# Adafruit_Latching_Relay_FeatherWing.net
KiCad netlist of a schematic drawn in EAGLE
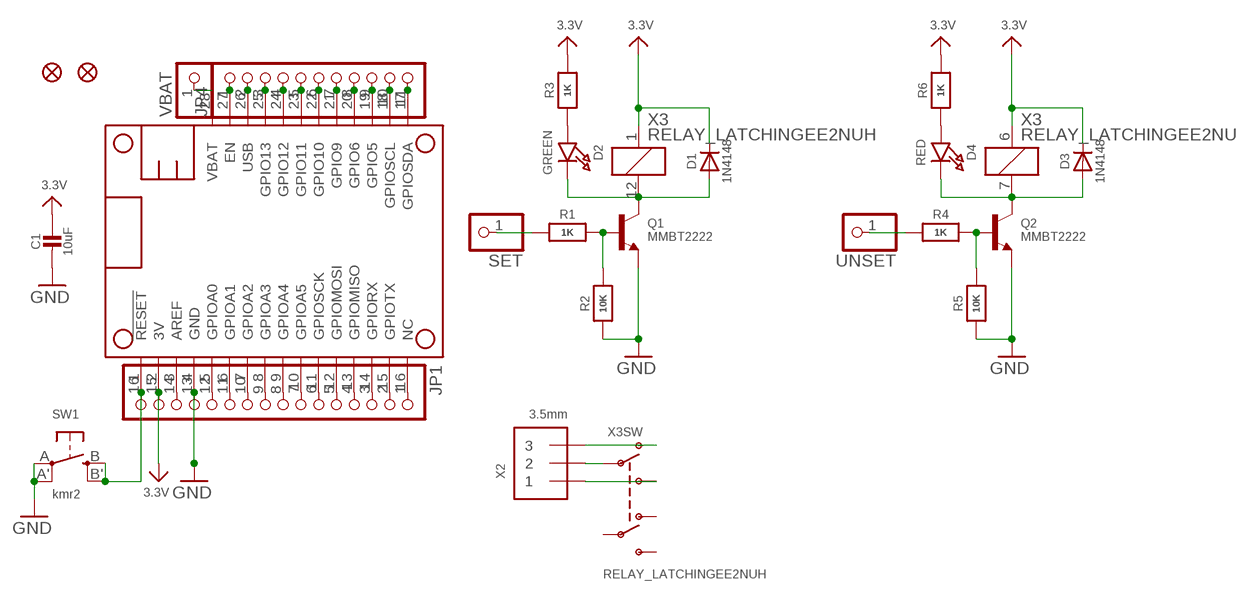
[diagram p0: schematic, sheet 1]

(export (version "E")
  (design (tool "Eeschema 10.0.6"))
  (components
    (comp (ref "C1")
      (value "10uF")
      (footprint "eagle-import:0805-NO")
      (libsource (lib "eagle-import") (part "CAP_CERAMIC0805-NOOUTLINE"))
    )
    (comp (ref "D1")
      (value "1N4148")
      (footprint "eagle-import:SOD-323")
      (libsource (lib "eagle-import") (part "DIODESOD-323"))
    )
    (comp (ref "D2")
      (value "GREEN")
      (footprint "eagle-import:CHIPLED_0805_NOOUTLINE")
      (libsource (lib "eagle-import") (part "LED0805_NOOUTLINE"))
    )
    (comp (ref "D3")
      (value "1N4148")
      (footprint "eagle-import:SOD-323")
      (libsource (lib "eagle-import") (part "DIODESOD-323"))
    )
    (comp (ref "D4")
      (value "RED")
      (footprint "eagle-import:CHIPLED_0805_NOOUTLINE")
      (libsource (lib "eagle-import") (part "LED0805_NOOUTLINE"))
    )
    (comp (ref "FID2")
      (value "FIDUCIAL\"\"")
      (footprint "eagle-import:FIDUCIAL_1MM")
      (libsource (lib "eagle-import") (part "FIDUCIAL{dblquote}{dblquote}"))
    )
    (comp (ref "FID3")
      (value "FIDUCIAL\"\"")
      (footprint "eagle-import:FIDUCIAL_1MM")
      (libsource (lib "eagle-import") (part "FIDUCIAL{dblquote}{dblquote}"))
    )
    (comp (ref "JP1")
      (value "HEADER-1X16ROUND")
      (footprint "eagle-import:1X16_ROUND")
      (libsource (lib "eagle-import") (part "HEADER-1X16ROUND"))
    )
    (comp (ref "JP4")
      (value "HEADER-1X11")
      (footprint "eagle-import:1X11_ROUND")
      (libsource (lib "eagle-import") (part "HEADER-1X11"))
    )
    (comp (ref "MS1")
      (value "MICROSHIELD")
      (footprint "eagle-import:MICROSHIELD")
      (libsource (lib "eagle-import") (part "MICROSHIELD"))
    )
    (comp (ref "Q1")
      (value "MMBT2222")
      (footprint "eagle-import:SOT23-R")
      (libsource (lib "eagle-import") (part "TRANSISTOR_NPN"))
    )
    (comp (ref "Q2")
      (value "MMBT2222")
      (footprint "eagle-import:SOT23-R")
      (libsource (lib "eagle-import") (part "TRANSISTOR_NPN"))
    )
    (comp (ref "R1")
      (value "1K")
      (footprint "eagle-import:0805-NO")
      (libsource (lib "eagle-import") (part "RESISTOR0805_NOOUTLINE"))
    )
    (comp (ref "R2")
      (value "10K")
      (footprint "eagle-import:0805-NO")
      (libsource (lib "eagle-import") (part "RESISTOR0805_NOOUTLINE"))
    )
    (comp (ref "R3")
      (value "1K")
      (footprint "eagle-import:0805-NO")
      (libsource (lib "eagle-import") (part "RESISTOR0805_NOOUTLINE"))
    )
    (comp (ref "R4")
      (value "1K")
      (footprint "eagle-import:0805-NO")
      (libsource (lib "eagle-import") (part "RESISTOR0805_NOOUTLINE"))
    )
    (comp (ref "R5")
      (value "10K")
      (footprint "eagle-import:0805-NO")
      (libsource (lib "eagle-import") (part "RESISTOR0805_NOOUTLINE"))
    )
    (comp (ref "R6")
      (value "1K")
      (footprint "eagle-import:0805-NO")
      (libsource (lib "eagle-import") (part "RESISTOR0805_NOOUTLINE"))
    )
    (comp (ref "SET")
      (value "HEADER-1X1ROUND")
      (footprint "eagle-import:1X01_ROUND")
      (libsource (lib "eagle-import") (part "HEADER-1X1ROUND"))
    )
    (comp (ref "SW1")
      (value "kmr2")
      (footprint "eagle-import:BTN_KMR2_4.6X2.8")
      (libsource (lib "eagle-import") (part "SWITCH_TACT_SMT4.6X2.8"))
    )
    (comp (ref "UNSET")
      (value "HEADER-1X1ROUND")
      (footprint "eagle-import:1X01_ROUND")
      (libsource (lib "eagle-import") (part "HEADER-1X1ROUND"))
    )
    (comp (ref "VBAT")
      (value "HEADER-1X1ROUND")
      (footprint "eagle-import:1X01_ROUND")
      (libsource (lib "eagle-import") (part "HEADER-1X1ROUND"))
    )
    (comp (ref "X2")
      (value "3.5mm")
      (footprint "eagle-import:TERMBLOCK_1X3-3.5MM")
      (libsource (lib "eagle-import") (part "TERMBLOCK_1X3"))
    )
    (comp (ref "X3")
      (value "RELAY_LATCHINGEE2NUH")
      (footprint "eagle-import:RELAY_EE2_LATCH")
      (libsource (lib "eagle-import") (part "RELAY_LATCHINGEE2NUH"))
    )
  )
  (nets
    (net (code "1") (name "3.3V") (class "Default")
      (node (ref "C1") (pin "1") (pinfunction "1_1") (pintype "passive"))
      (node (ref "D1") (pin "C") (pinfunction "C_C") (pintype "passive"))
      (node (ref "D3") (pin "C") (pinfunction "C_C") (pintype "passive"))
      (node (ref "JP1") (pin "15") (pinfunction "15_15") (pintype "passive"))
      (node (ref "MS1") (pin "2") (pinfunction "3V_2") (pintype "power_in"))
      (node (ref "R3") (pin "2") (pinfunction "2_2") (pintype "passive"))
      (node (ref "R6") (pin "2") (pinfunction "2_2") (pintype "passive"))
      (node (ref "X3") (pin "1") (pinfunction "1_1") (pintype "passive"))
      (node (ref "X3") (pin "6") (pinfunction "1_6") (pintype "passive"))
    )
    (net (code "2") (name "GND") (class "Default")
      (node (ref "C1") (pin "2") (pinfunction "2_2") (pintype "passive"))
      (node (ref "JP1") (pin "13") (pinfunction "13_13") (pintype "passive"))
      (node (ref "MS1") (pin "4") (pinfunction "GND_4") (pintype "power_in"))
      (node (ref "Q1") (pin "2") (pinfunction "E_2") (pintype "passive"))
      (node (ref "Q2") (pin "2") (pinfunction "E_2") (pintype "passive"))
      (node (ref "R2") (pin "1") (pinfunction "1_1") (pintype "passive"))
      (node (ref "R5") (pin "1") (pinfunction "1_1") (pintype "passive"))
      (node (ref "SW1") (pin "A") (pinfunction "P_A") (pintype "passive"))
      (node (ref "SW1") (pin "A'") (pinfunction "P1_A'") (pintype "passive"))
    )
    (net (code "3") (name "Net-(D2-PadA)") (class "Default")
      (node (ref "D2") (pin "A") (pinfunction "A_A") (pintype "passive"))
      (node (ref "R3") (pin "1") (pinfunction "1_1") (pintype "passive"))
    )
    (net (code "4") (name "Net-(D4-PadA)") (class "Default")
      (node (ref "D4") (pin "A") (pinfunction "A_A") (pintype "passive"))
      (node (ref "R6") (pin "1") (pinfunction "1_1") (pintype "passive"))
    )
    (net (code "5") (name "Net-(MS1-AREF)") (class "Default")
      (node (ref "JP1") (pin "14") (pinfunction "14_14") (pintype "passive"))
      (node (ref "MS1") (pin "3") (pinfunction "AREF_3") (pintype "passive"))
    )
    (net (code "6") (name "Net-(MS1-EN)") (class "Default")
      (node (ref "JP4") (pin "1") (pinfunction "1_1") (pintype "passive"))
      (node (ref "MS1") (pin "27") (pinfunction "EN_27") (pintype "passive"))
    )
    (net (code "7") (name "Net-(MS1-GPIO5)") (class "Default")
      (node (ref "JP4") (pin "9") (pinfunction "9_9") (pintype "passive"))
      (node (ref "MS1") (pin "19") (pinfunction "GPIO5_19") (pintype "bidirectional"))
    )
    (net (code "8") (name "Net-(MS1-GPIO6)") (class "Default")
      (node (ref "JP4") (pin "8") (pinfunction "8_8") (pintype "passive"))
      (node (ref "MS1") (pin "20") (pinfunction "GPIO6_20") (pintype "bidirectional"))
    )
    (net (code "9") (name "Net-(MS1-GPIO9)") (class "Default")
      (node (ref "JP4") (pin "7") (pinfunction "7_7") (pintype "passive"))
      (node (ref "MS1") (pin "21") (pinfunction "GPIO9_21") (pintype "bidirectional"))
    )
    (net (code "10") (name "Net-(MS1-GPIO10)") (class "Default")
      (node (ref "JP4") (pin "6") (pinfunction "6_6") (pintype "passive"))
      (node (ref "MS1") (pin "22") (pinfunction "GPIO10_22") (pintype "bidirectional"))
    )
    (net (code "11") (name "Net-(MS1-GPIO11)") (class "Default")
      (node (ref "JP4") (pin "5") (pinfunction "5_5") (pintype "passive"))
      (node (ref "MS1") (pin "23") (pinfunction "GPIO11_23") (pintype "bidirectional"))
    )
    (net (code "12") (name "Net-(MS1-GPIO12)") (class "Default")
      (node (ref "JP4") (pin "4") (pinfunction "4_4") (pintype "passive"))
      (node (ref "MS1") (pin "24") (pinfunction "GPIO12_24") (pintype "bidirectional"))
    )
    (net (code "13") (name "Net-(MS1-GPIO13)") (class "Default")
      (node (ref "JP4") (pin "3") (pinfunction "3_3") (pintype "passive"))
      (node (ref "MS1") (pin "25") (pinfunction "GPIO13_25") (pintype "bidirectional"))
    )
    (net (code "14") (name "Net-(MS1-GPIOA0)") (class "Default")
      (node (ref "JP1") (pin "12") (pinfunction "12_12") (pintype "passive"))
      (node (ref "MS1") (pin "5") (pinfunction "GPIOA0_5") (pintype "bidirectional"))
    )
    (net (code "15") (name "Net-(MS1-GPIOA1)") (class "Default")
      (node (ref "JP1") (pin "11") (pinfunction "11_11") (pintype "passive"))
      (node (ref "MS1") (pin "6") (pinfunction "GPIOA1_6") (pintype "bidirectional"))
    )
    (net (code "16") (name "Net-(MS1-GPIOA2)") (class "Default")
      (node (ref "JP1") (pin "10") (pinfunction "10_10") (pintype "passive"))
      (node (ref "MS1") (pin "7") (pinfunction "GPIOA2_7") (pintype "bidirectional"))
    )
    (net (code "17") (name "Net-(MS1-GPIOA3)") (class "Default")
      (node (ref "JP1") (pin "9") (pinfunction "9_9") (pintype "passive"))
      (node (ref "MS1") (pin "8") (pinfunction "GPIOA3_8") (pintype "bidirectional"))
    )
    (net (code "18") (name "Net-(MS1-GPIOA4)") (class "Default")
      (node (ref "JP1") (pin "8") (pinfunction "8_8") (pintype "passive"))
      (node (ref "MS1") (pin "9") (pinfunction "GPIOA4_9") (pintype "bidirectional"))
    )
    (net (code "19") (name "Net-(MS1-GPIOA5)") (class "Default")
      (node (ref "JP1") (pin "7") (pinfunction "7_7") (pintype "passive"))
      (node (ref "MS1") (pin "10") (pinfunction "GPIOA5_10") (pintype "bidirectional"))
    )
    (net (code "20") (name "Net-(MS1-GPIOMISO)") (class "Default")
      (node (ref "JP1") (pin "4") (pinfunction "4_4") (pintype "passive"))
      (node (ref "MS1") (pin "13") (pinfunction "GPIOMISO_13") (pintype "bidirectional"))
    )
    (net (code "21") (name "Net-(MS1-GPIOMOSI)") (class "Default")
      (node (ref "JP1") (pin "5") (pinfunction "5_5") (pintype "passive"))
      (node (ref "MS1") (pin "12") (pinfunction "GPIOMOSI_12") (pintype "bidirectional"))
    )
    (net (code "22") (name "Net-(MS1-GPIORX)") (class "Default")
      (node (ref "JP1") (pin "3") (pinfunction "3_3") (pintype "passive"))
      (node (ref "MS1") (pin "14") (pinfunction "GPIORX_14") (pintype "bidirectional"))
    )
    (net (code "23") (name "Net-(MS1-GPIOSCK)") (class "Default")
      (node (ref "JP1") (pin "6") (pinfunction "6_6") (pintype "passive"))
      (node (ref "MS1") (pin "11") (pinfunction "GPIOSCK_11") (pintype "bidirectional"))
    )
    (net (code "24") (name "Net-(MS1-GPIOSCL)") (class "Default")
      (node (ref "JP4") (pin "10") (pinfunction "10_10") (pintype "passive"))
      (node (ref "MS1") (pin "18") (pinfunction "GPIOSCL_18") (pintype "bidirectional"))
    )
    (net (code "25") (name "Net-(MS1-GPIOSDA)") (class "Default")
      (node (ref "JP4") (pin "11") (pinfunction "11_11") (pintype "passive"))
      (node (ref "MS1") (pin "17") (pinfunction "GPIOSDA_17") (pintype "bidirectional"))
    )
    (net (code "26") (name "Net-(MS1-GPIOTX)") (class "Default")
      (node (ref "JP1") (pin "2") (pinfunction "2_2") (pintype "passive"))
      (node (ref "MS1") (pin "15") (pinfunction "GPIOTX_15") (pintype "bidirectional"))
    )
    (net (code "27") (name "Net-(MS1-NC)") (class "Default")
      (node (ref "JP1") (pin "1") (pinfunction "1_1") (pintype "passive"))
      (node (ref "MS1") (pin "16") (pinfunction "NC_16") (pintype "passive"))
    )
    (net (code "28") (name "Net-(MS1-USB)") (class "Default")
      (node (ref "JP4") (pin "2") (pinfunction "2_2") (pintype "passive"))
      (node (ref "MS1") (pin "26") (pinfunction "USB_26") (pintype "power_in"))
    )
    (net (code "29") (name "Net-(MS1-VBAT)") (class "Default")
      (node (ref "MS1") (pin "28") (pinfunction "VBAT_28") (pintype "power_in"))
      (node (ref "VBAT") (pin "1") (pinfunction "1_1") (pintype "passive"))
    )
    (net (code "30") (name "Net-(MS1-~{RESET})") (class "Default")
      (node (ref "JP1") (pin "16") (pinfunction "16_16") (pintype "passive"))
      (node (ref "MS1") (pin "1") (pinfunction "~{RESET}_1") (pintype "input"))
      (node (ref "SW1") (pin "B") (pinfunction "S_B") (pintype "passive"))
      (node (ref "SW1") (pin "B'") (pinfunction "S1_B'") (pintype "passive"))
    )
    (net (code "31") (name "Net-(Q1-B)") (class "Default")
      (node (ref "Q1") (pin "1") (pinfunction "B_1") (pintype "passive"))
      (node (ref "R1") (pin "2") (pinfunction "2_2") (pintype "passive"))
      (node (ref "R2") (pin "2") (pinfunction "2_2") (pintype "passive"))
    )
    (net (code "32") (name "Net-(Q1-C)") (class "Default")
      (node (ref "D1") (pin "A") (pinfunction "A_A") (pintype "passive"))
      (node (ref "D2") (pin "C") (pinfunction "C_C") (pintype "passive"))
      (node (ref "Q1") (pin "3") (pinfunction "C_3") (pintype "passive"))
      (node (ref "X3") (pin "12") (pinfunction "2_12") (pintype "passive"))
    )
    (net (code "33") (name "Net-(Q2-B)") (class "Default")
      (node (ref "Q2") (pin "1") (pinfunction "B_1") (pintype "passive"))
      (node (ref "R4") (pin "2") (pinfunction "2_2") (pintype "passive"))
      (node (ref "R5") (pin "2") (pinfunction "2_2") (pintype "passive"))
    )
    (net (code "34") (name "Net-(Q2-C)") (class "Default")
      (node (ref "D3") (pin "A") (pinfunction "A_A") (pintype "passive"))
      (node (ref "D4") (pin "C") (pinfunction "C_C") (pintype "passive"))
      (node (ref "Q2") (pin "3") (pinfunction "C_3") (pintype "passive"))
      (node (ref "X3") (pin "7") (pinfunction "2_7") (pintype "passive"))
    )
    (net (code "35") (name "Net-(R1-Pad1)") (class "Default")
      (node (ref "R1") (pin "1") (pinfunction "1_1") (pintype "passive"))
      (node (ref "SET") (pin "1") (pinfunction "1_1") (pintype "passive"))
    )
    (net (code "36") (name "Net-(R4-Pad1)") (class "Default")
      (node (ref "R4") (pin "1") (pinfunction "1_1") (pintype "passive"))
      (node (ref "UNSET") (pin "1") (pinfunction "1_1") (pintype "passive"))
    )
    (net (code "37") (name "Net-(X3C-O1)") (class "Default")
      (node (ref "X2") (pin "3") (pinfunction "3_3") (pintype "passive"))
      (node (ref "X3") (pin "10") (pinfunction "O1_10") (pintype "passive"))
    )
    (net (code "38") (name "Net-(X3C-P1)") (class "Default")
      (node (ref "X2") (pin "2") (pinfunction "2_2") (pintype "passive"))
      (node (ref "X3") (pin "9") (pinfunction "P1_9") (pintype "passive"))
    )
    (net (code "39") (name "Net-(X3C-S1)") (class "Default")
      (node (ref "X2") (pin "1") (pinfunction "1_1") (pintype "passive"))
      (node (ref "X3") (pin "8") (pinfunction "S1_8") (pintype "passive"))
    )
    (net (code "40") (name "unconnected-(X3C-O2-Pad3)") (class "Default")
      (node (ref "X3") (pin "3") (pinfunction "O2_3") (pintype "passive"))
    )
    (net (code "41") (name "unconnected-(X3C-P2-Pad4)") (class "Default")
      (node (ref "X3") (pin "4") (pinfunction "P2_4") (pintype "passive"))
    )
    (net (code "42") (name "unconnected-(X3C-S2-Pad5)") (class "Default")
      (node (ref "X3") (pin "5") (pinfunction "S2_5") (pintype "passive"))
    )
  )
)
